# MultiWiiChassis.net
KiCad netlist of a schematic drawn in EAGLE
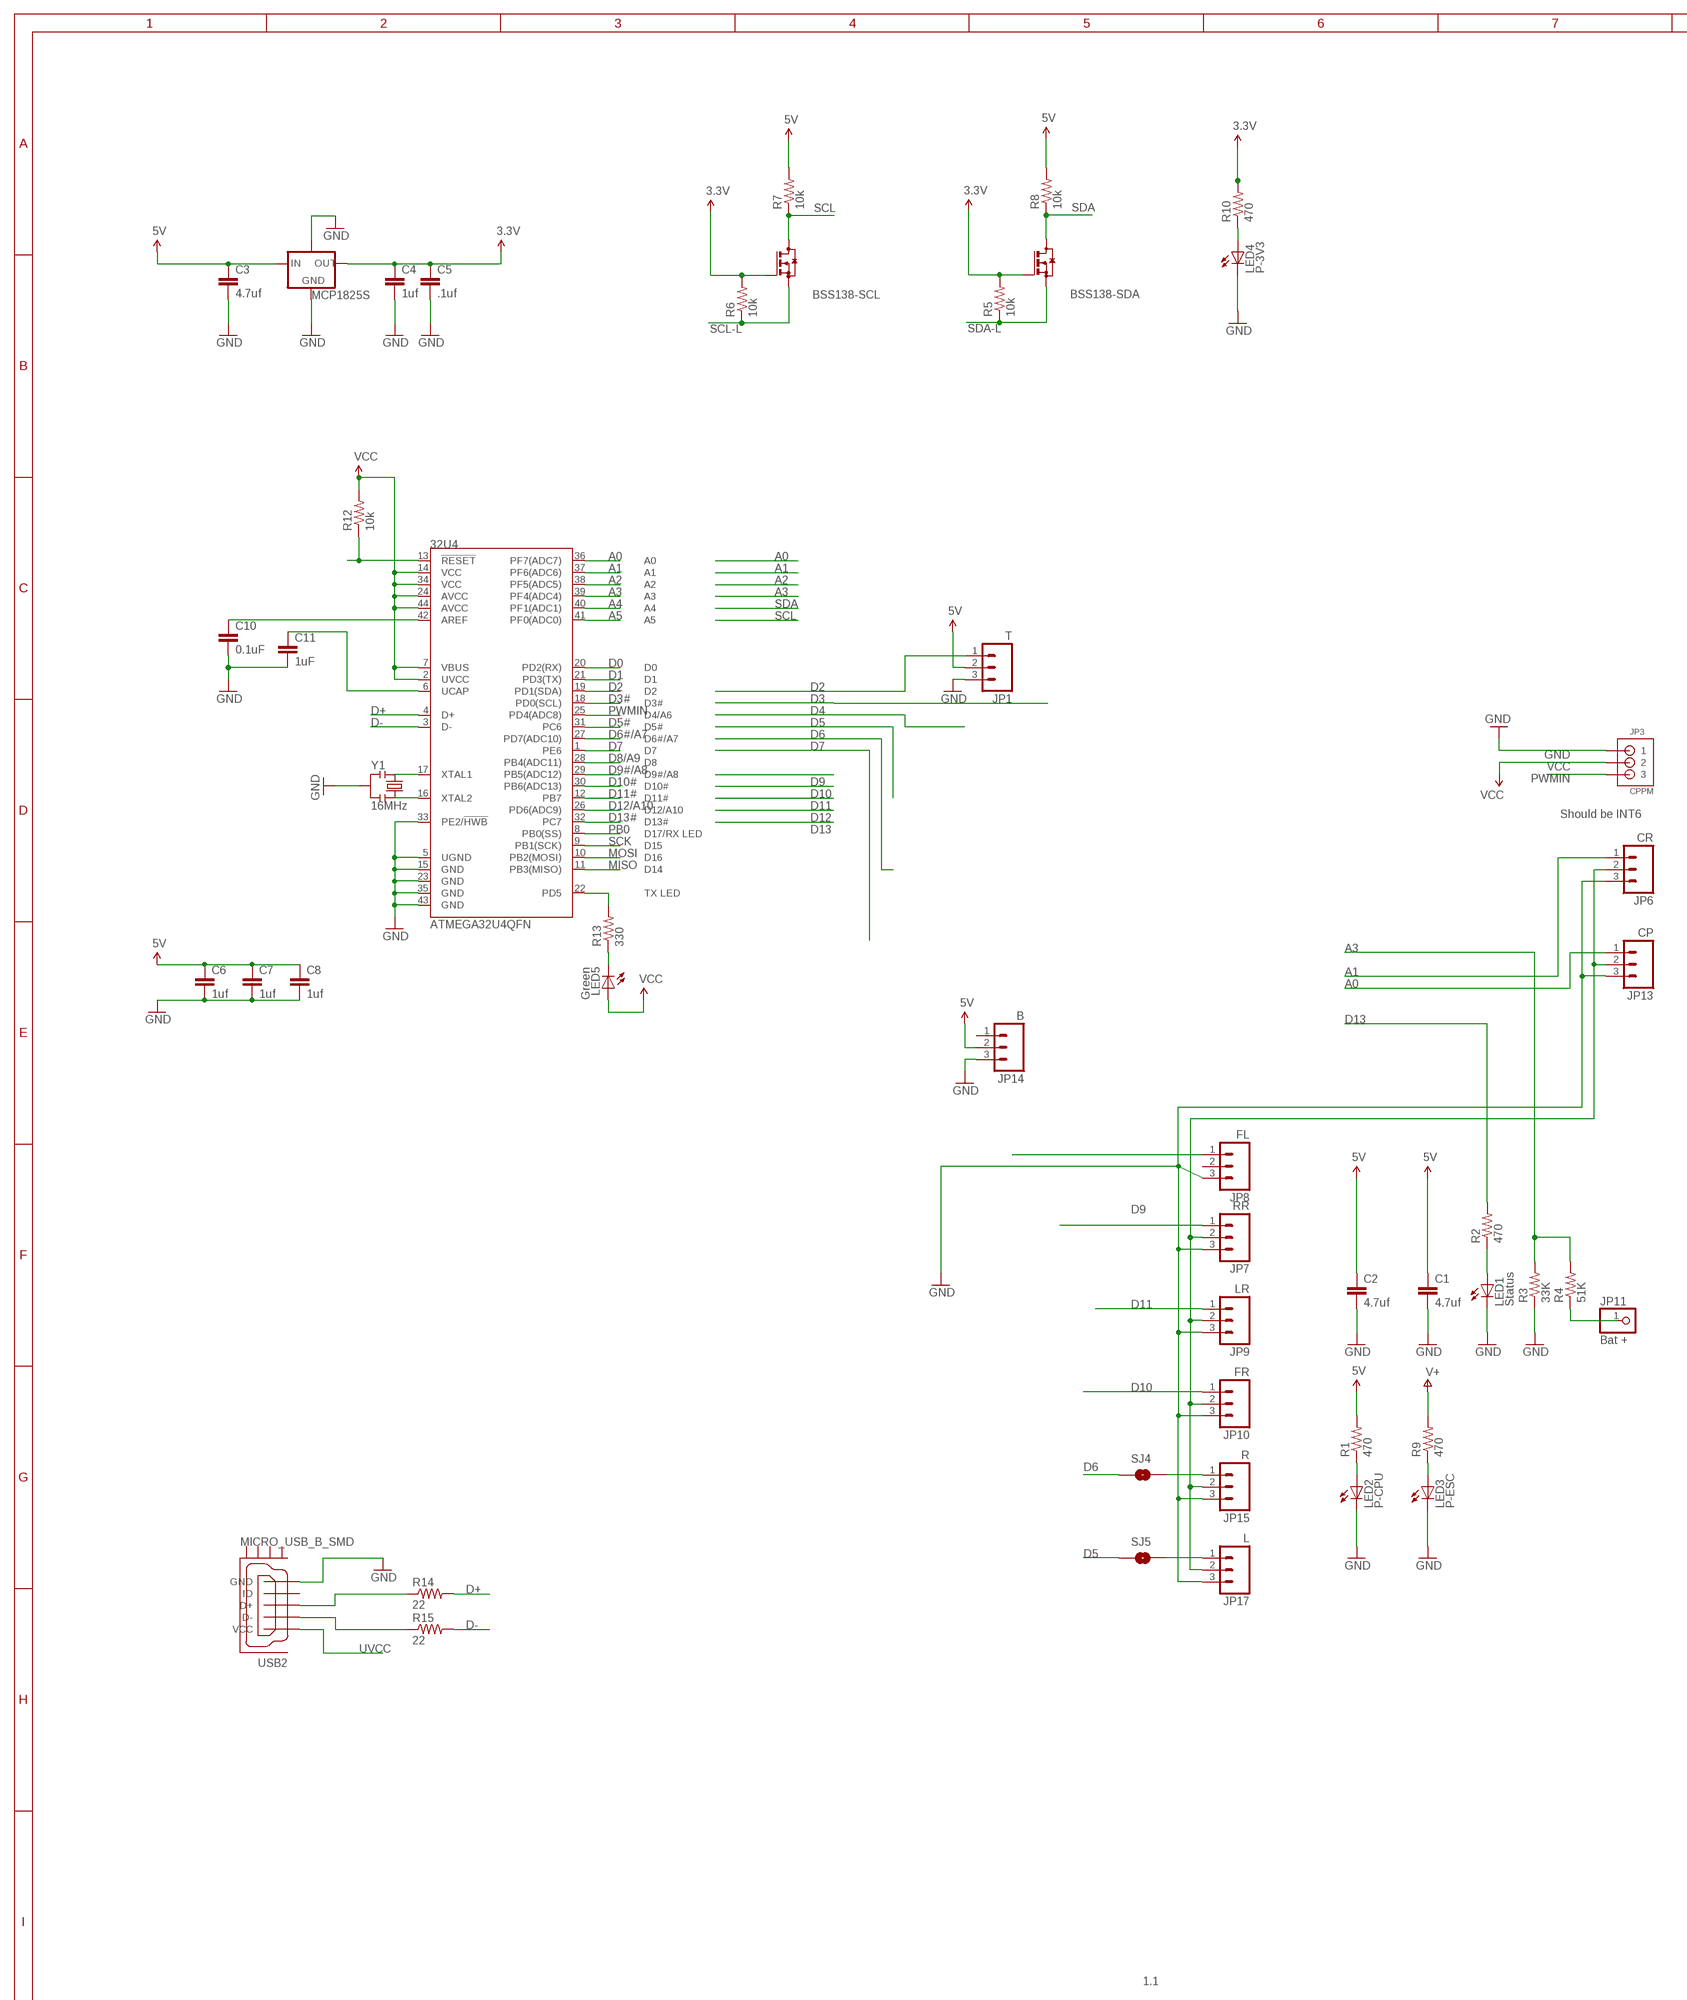
[diagram p0: schematic, sheet 1, part 1 of 2]
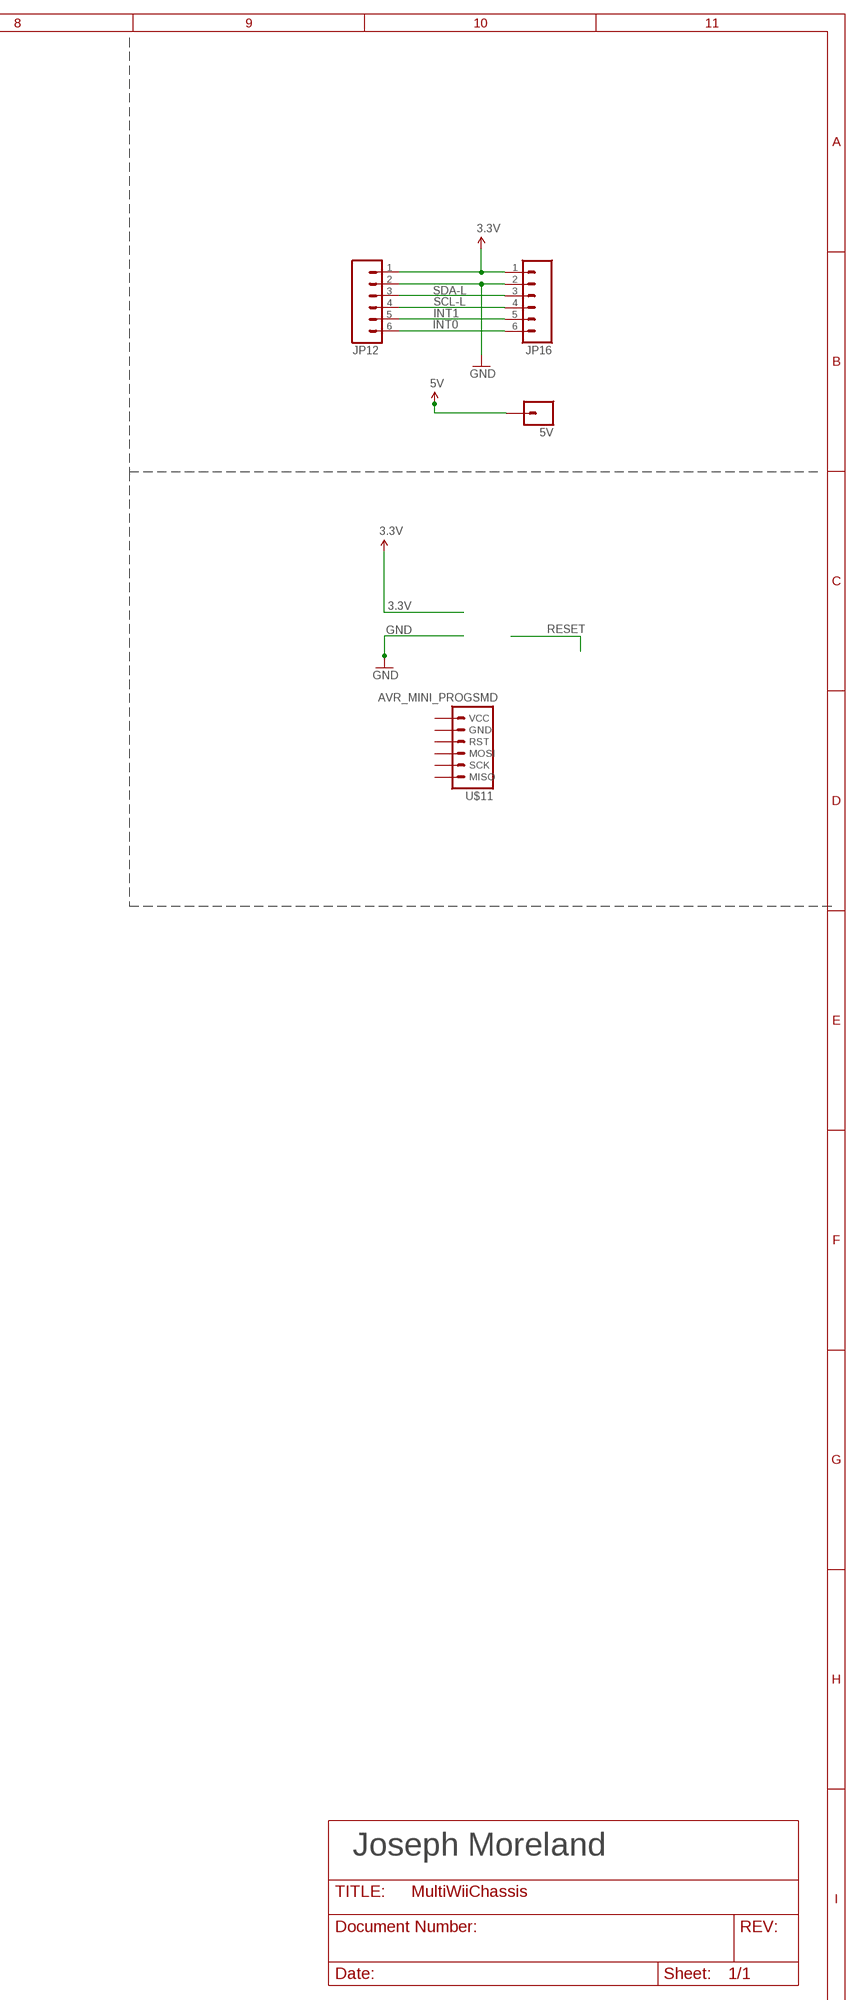
[diagram p1: schematic, sheet 1, part 2 of 2]

(export (version "E")
  (design (tool "Eeschema 10.0.6"))
  (components
    (comp (ref "5V")
      (value "M01PTH")
      (footprint "eagle-import:1X01")
      (libsource (lib "eagle-import") (part "M01PTH"))
    )
    (comp (ref "32U4")
      (value "ATMEGA32U4QFN")
      (footprint "eagle-import:SPARKFUN-DIGITALIC_QFN-44")
      (fields (field (name "PARTNO") "ATMEGA32U4-MU"))
      (libsource (lib "eagle-import") (part "ATMEGA32U4QFN"))
    )
    (comp (ref "BSS138-SCL")
      (value "BSS138BOTTOM")
      (footprint "eagle-import:SOT23_BOT")
      (libsource (lib "eagle-import") (part "BSS138BOTTOM"))
    )
    (comp (ref "BSS138-SDA")
      (value "BSS138BOTTOM")
      (footprint "eagle-import:SOT23_BOT")
      (libsource (lib "eagle-import") (part "BSS138BOTTOM"))
    )
    (comp (ref "C1")
      (value "4.7uf")
      (footprint "eagle-import:0603-CAP")
      (libsource (lib "eagle-import") (part "CAP0603-CAP"))
    )
    (comp (ref "C2")
      (value "4.7uf")
      (footprint "eagle-import:0603-CAP")
      (libsource (lib "eagle-import") (part "CAP0603-CAP"))
    )
    (comp (ref "C3")
      (value "4.7uf")
      (footprint "eagle-import:0603-CAP")
      (libsource (lib "eagle-import") (part "CAP0603-CAP"))
    )
    (comp (ref "C4")
      (value "1uf")
      (footprint "eagle-import:0603-CAP")
      (libsource (lib "eagle-import") (part "CAP0603-CAP"))
    )
    (comp (ref "C5")
      (value ".1uf")
      (footprint "eagle-import:0603-CAP")
      (libsource (lib "eagle-import") (part "CAP0603-CAP"))
    )
    (comp (ref "C6")
      (value "1uf")
      (footprint "eagle-import:0603-CAP")
      (libsource (lib "eagle-import") (part "CAP0603-CAP"))
    )
    (comp (ref "C7")
      (value "1uf")
      (footprint "eagle-import:0603-CAP")
      (libsource (lib "eagle-import") (part "CAP0603-CAP"))
    )
    (comp (ref "C8")
      (value "1uf")
      (footprint "eagle-import:0603-CAP")
      (libsource (lib "eagle-import") (part "CAP0603-CAP"))
    )
    (comp (ref "C10")
      (value "0.1uF")
      (footprint "eagle-import:0603-CAP")
      (fields (field (name "PARTNO") "C0603C104K8RACTU"))
      (libsource (lib "eagle-import") (part "SparkFun-Capacitors_CAP0603-CAP"))
    )
    (comp (ref "C11")
      (value "1uF")
      (footprint "eagle-import:0402-CAP")
      (fields (field (name "PARTNO") "LMK105BJ105KV-F"))
      (libsource (lib "eagle-import") (part "SparkFun-Capacitors_CAP0402-CAP"))
    )
    (comp (ref "JP1")
      (value "T")
      (footprint "eagle-import:1X03")
      (libsource (lib "eagle-import") (part "M03PTH"))
    )
    (comp (ref "JP3")
      (value "CPPM")
      (footprint "eagle-import:B3B-ZR")
      (fields (field (name "PARTNO") "M20-9990346"))
      (libsource (lib "eagle-import") (part "B3B-ZR"))
    )
    (comp (ref "JP6")
      (value "CR")
      (footprint "eagle-import:1X03")
      (libsource (lib "eagle-import") (part "M03PTH"))
    )
    (comp (ref "JP7")
      (value "RR")
      (footprint "eagle-import:1X03")
      (libsource (lib "eagle-import") (part "M03PTH"))
    )
    (comp (ref "JP8")
      (value "FL")
      (footprint "eagle-import:1X03")
      (libsource (lib "eagle-import") (part "M03PTH"))
    )
    (comp (ref "JP9")
      (value "LR")
      (footprint "eagle-import:1X03")
      (libsource (lib "eagle-import") (part "M03PTH"))
    )
    (comp (ref "JP10")
      (value "FR")
      (footprint "eagle-import:1X03")
      (libsource (lib "eagle-import") (part "M03PTH"))
    )
    (comp (ref "JP11")
      (value "Bat +")
      (footprint "eagle-import:1X01")
      (libsource (lib "eagle-import") (part "PINHD-1X1"))
    )
    (comp (ref "JP12")
      (value "M06LOCK")
      (footprint "eagle-import:1X06_LOCK")
      (libsource (lib "eagle-import") (part "M06LOCK"))
    )
    (comp (ref "JP13")
      (value "CP")
      (footprint "eagle-import:1X03")
      (libsource (lib "eagle-import") (part "M03PTH"))
    )
    (comp (ref "JP14")
      (value "B")
      (footprint "eagle-import:1X03")
      (libsource (lib "eagle-import") (part "M03PTH"))
    )
    (comp (ref "JP15")
      (value "R")
      (footprint "eagle-import:1X03")
      (libsource (lib "eagle-import") (part "M03PTH"))
    )
    (comp (ref "JP16")
      (value "M06LOCK")
      (footprint "eagle-import:1X06_LOCK")
      (libsource (lib "eagle-import") (part "M06LOCK"))
    )
    (comp (ref "JP17")
      (value "L")
      (footprint "eagle-import:1X03")
      (libsource (lib "eagle-import") (part "M03PTH"))
    )
    (comp (ref "LED1")
      (value "Status")
      (footprint "eagle-import:LED-1206")
      (libsource (lib "eagle-import") (part "LED1206"))
    )
    (comp (ref "LED2")
      (value "P-CPU")
      (footprint "eagle-import:LED-1206")
      (libsource (lib "eagle-import") (part "LED1206"))
    )
    (comp (ref "LED3")
      (value "P-ESC")
      (footprint "eagle-import:LED-1206")
      (libsource (lib "eagle-import") (part "LED1206"))
    )
    (comp (ref "LED4")
      (value "P-3V3")
      (footprint "eagle-import:LED-1206")
      (libsource (lib "eagle-import") (part "LED1206"))
    )
    (comp (ref "LED5")
      (value "Green")
      (footprint "eagle-import:LED-0603")
      (fields (field (name "PARTNO") "LTST-C190KGKT"))
      (libsource (lib "eagle-import") (part "SparkFun-LED_LED0603"))
    )
    (comp (ref "MCP1825S")
      (value "V_REG_MCP1825S")
      (footprint "eagle-import:SOT223_BOT")
      (libsource (lib "eagle-import") (part "V_REG_MCP1825SBOTTOM"))
    )
    (comp (ref "R1")
      (value "470")
      (footprint "eagle-import:0603-RES")
      (libsource (lib "eagle-import") (part "RESISTOR0603-RES"))
    )
    (comp (ref "R2")
      (value "470")
      (footprint "eagle-import:0603-RES")
      (libsource (lib "eagle-import") (part "RESISTOR0603-RES"))
    )
    (comp (ref "R3")
      (value "33K")
      (footprint "eagle-import:0603-RES")
      (libsource (lib "eagle-import") (part "RESISTOR0603-RES"))
    )
    (comp (ref "R4")
      (value "51K")
      (footprint "eagle-import:0805")
      (libsource (lib "eagle-import") (part "RESISTOR0805-RES"))
    )
    (comp (ref "R5")
      (value "10k")
      (footprint "eagle-import:0805")
      (libsource (lib "eagle-import") (part "RESISTOR0805-RES"))
    )
    (comp (ref "R6")
      (value "10k")
      (footprint "eagle-import:0805")
      (libsource (lib "eagle-import") (part "RESISTOR0805-RES"))
    )
    (comp (ref "R7")
      (value "10k")
      (footprint "eagle-import:0805")
      (libsource (lib "eagle-import") (part "RESISTOR0805-RES"))
    )
    (comp (ref "R8")
      (value "10k")
      (footprint "eagle-import:0805")
      (libsource (lib "eagle-import") (part "RESISTOR0805-RES"))
    )
    (comp (ref "R9")
      (value "470")
      (footprint "eagle-import:0805")
      (libsource (lib "eagle-import") (part "RESISTOR0805-RES"))
    )
    (comp (ref "R10")
      (value "470")
      (footprint "eagle-import:0805")
      (libsource (lib "eagle-import") (part "RESISTOR0805-RES"))
    )
    (comp (ref "R12")
      (value "10k")
      (footprint "eagle-import:0402-RES")
      (fields (field (name "PARTNO") "CRCW040210K0FKED"))
      (libsource (lib "eagle-import") (part "SparkFun-Resistors_RESISTOR0402-RES"))
    )
    (comp (ref "R13")
      (value "330")
      (footprint "eagle-import:0402-RES")
      (fields (field (name "PARTNO") "CRCW0402330RJNED"))
      (libsource (lib "eagle-import") (part "SparkFun-Resistors_RESISTOR0402-RES"))
    )
    (comp (ref "R14")
      (value "22")
      (footprint "eagle-import:0402-RES")
      (fields (field (name "PARTNO") "CRCW040222R0JNED"))
      (libsource (lib "eagle-import") (part "SparkFun-Resistors_RESISTOR0402-RES"))
    )
    (comp (ref "R15")
      (value "22")
      (footprint "eagle-import:0402-RES")
      (fields (field (name "PARTNO") "CRCW040222R0JNED"))
      (libsource (lib "eagle-import") (part "SparkFun-Resistors_RESISTOR0402-RES"))
    )
    (comp (ref "SJ4")
      (value "SOLDERJUMPERNO")
      (footprint "eagle-import:SJ_2S-NO")
      (libsource (lib "eagle-import") (part "SOLDERJUMPERNO"))
    )
    (comp (ref "SJ5")
      (value "SOLDERJUMPERNO")
      (footprint "eagle-import:SJ_2S-NO")
      (libsource (lib "eagle-import") (part "SOLDERJUMPERNO"))
    )
    (comp (ref "U$11")
      (value "AVR_MINI_PROGSMD")
      (footprint "eagle-import:AVR_MINI_PROG")
      (libsource (lib "eagle-import") (part "AVR_MINI_PROGSMD"))
    )
    (comp (ref "USB2")
      (value "MICRO_USB_B_SMD")
      (footprint "eagle-import:MOLEX_MICRO_USB_B_BOTTOM_MOUNT")
      (fields (field (name "PARTNO") "473460001"))
      (libsource (lib "eagle-import") (part "MICRO_USB_B_SMD"))
    )
    (comp (ref "Y1")
      (value "16MHz")
      (footprint "eagle-import:RESONATOR-SMD")
      (fields (field (name "PARTNO") "CSTCE16M0V53-R0"))
      (libsource (lib "eagle-import") (part "RESONATOR16MHZ"))
    )
  )
  (nets
    (net (code "1") (name "/A0") (class "Default")
      (node (ref "32U4") (pin "36") (pinfunction "PF7(ADC7)_36") (pintype "bidirectional"))
      (node (ref "JP13") (pin "1") (pinfunction "1_1") (pintype "passive"))
    )
    (net (code "2") (name "/A1") (class "Default")
      (node (ref "32U4") (pin "37") (pinfunction "PF6(ADC6)_37") (pintype "bidirectional"))
      (node (ref "JP6") (pin "1") (pinfunction "1_1") (pintype "passive"))
    )
    (net (code "3") (name "/A2") (class "Default")
      (node (ref "32U4") (pin "38") (pinfunction "PF5(ADC5)_38") (pintype "bidirectional"))
    )
    (net (code "4") (name "/A3") (class "Default")
      (node (ref "32U4") (pin "39") (pinfunction "PF4(ADC4)_39") (pintype "bidirectional"))
      (node (ref "R3") (pin "2") (pinfunction "2_2") (pintype "passive"))
      (node (ref "R4") (pin "2") (pinfunction "2_2") (pintype "passive"))
    )
    (net (code "5") (name "/A4") (class "Default")
      (node (ref "32U4") (pin "40") (pinfunction "PF1(ADC1)_40") (pintype "bidirectional"))
    )
    (net (code "6") (name "/A5") (class "Default")
      (node (ref "32U4") (pin "41") (pinfunction "PF0(ADC0)_41") (pintype "bidirectional"))
    )
    (net (code "7") (name "/D+") (class "Default")
      (node (ref "32U4") (pin "4") (pinfunction "D+_4") (pintype "bidirectional"))
      (node (ref "R14") (pin "2") (pinfunction "2_2") (pintype "passive"))
    )
    (net (code "8") (name "/D-") (class "Default")
      (node (ref "32U4") (pin "3") (pinfunction "D-_3") (pintype "bidirectional"))
      (node (ref "R15") (pin "2") (pinfunction "2_2") (pintype "passive"))
    )
    (net (code "9") (name "/D0") (class "Default")
      (node (ref "32U4") (pin "20") (pinfunction "PD2(RX)_20") (pintype "bidirectional"))
    )
    (net (code "10") (name "/D1") (class "Default")
      (node (ref "32U4") (pin "21") (pinfunction "PD3(TX)_21") (pintype "bidirectional"))
    )
    (net (code "11") (name "/D2") (class "Default")
      (node (ref "32U4") (pin "19") (pinfunction "PD1(SDA)_19") (pintype "bidirectional"))
      (node (ref "JP1") (pin "1") (pinfunction "1_1") (pintype "passive"))
    )
    (net (code "12") (name "/D3") (class "Default")
      (node (ref "JP8") (pin "1") (pinfunction "1_1") (pintype "passive"))
    )
    (net (code "13") (name "/D3#") (class "Default")
      (node (ref "32U4") (pin "18") (pinfunction "PD0(SCL)_18") (pintype "bidirectional"))
    )
    (net (code "15") (name "/D5") (class "Default")
      (node (ref "SJ5") (pin "1") (pinfunction "1_1") (pintype "passive"))
    )
    (net (code "16") (name "/D5#") (class "Default")
      (node (ref "32U4") (pin "31") (pinfunction "PC6_31") (pintype "bidirectional"))
    )
    (net (code "17") (name "/D6") (class "Default")
      (node (ref "SJ4") (pin "1") (pinfunction "1_1") (pintype "passive"))
    )
    (net (code "18") (name "/D6#{slash}A7") (class "Default")
      (node (ref "32U4") (pin "27") (pinfunction "PD7(ADC10)_27") (pintype "bidirectional"))
    )
    (net (code "19") (name "/D7") (class "Default")
      (node (ref "32U4") (pin "1") (pinfunction "PE6_1") (pintype "bidirectional"))
    )
    (net (code "20") (name "/D8{slash}A9") (class "Default")
      (node (ref "32U4") (pin "28") (pinfunction "PB4(ADC11)_28") (pintype "bidirectional"))
    )
    (net (code "21") (name "/D9") (class "Default")
      (node (ref "JP7") (pin "1") (pinfunction "1_1") (pintype "passive"))
    )
    (net (code "22") (name "/D9#{slash}A8") (class "Default")
      (node (ref "32U4") (pin "29") (pinfunction "PB5(ADC12)_29") (pintype "bidirectional"))
    )
    (net (code "23") (name "/D10") (class "Default")
      (node (ref "JP10") (pin "1") (pinfunction "1_1") (pintype "passive"))
    )
    (net (code "24") (name "/D10#") (class "Default")
      (node (ref "32U4") (pin "30") (pinfunction "PB6(ADC13)_30") (pintype "bidirectional"))
    )
    (net (code "25") (name "/D11") (class "Default")
      (node (ref "JP9") (pin "1") (pinfunction "1_1") (pintype "passive"))
    )
    (net (code "26") (name "/D11#") (class "Default")
      (node (ref "32U4") (pin "12") (pinfunction "PB7_12") (pintype "bidirectional"))
    )
    (net (code "28") (name "/D12{slash}A10") (class "Default")
      (node (ref "32U4") (pin "26") (pinfunction "PD6(ADC9)_26") (pintype "bidirectional"))
    )
    (net (code "29") (name "/D13") (class "Default")
      (node (ref "R2") (pin "2") (pinfunction "2_2") (pintype "passive"))
    )
    (net (code "30") (name "/D13#") (class "Default")
      (node (ref "32U4") (pin "32") (pinfunction "PC7_32") (pintype "bidirectional"))
    )
    (net (code "31") (name "/INT0") (class "Default")
      (node (ref "JP12") (pin "6") (pinfunction "6_6") (pintype "passive"))
      (node (ref "JP16") (pin "6") (pinfunction "6_6") (pintype "passive"))
    )
    (net (code "32") (name "/INT1") (class "Default")
      (node (ref "JP12") (pin "5") (pinfunction "5_5") (pintype "passive"))
      (node (ref "JP16") (pin "5") (pinfunction "5_5") (pintype "passive"))
    )
    (net (code "33") (name "/MISO") (class "Default")
      (node (ref "32U4") (pin "11") (pinfunction "PB3(MISO)_11") (pintype "bidirectional"))
    )
    (net (code "34") (name "/MOSI") (class "Default")
      (node (ref "32U4") (pin "10") (pinfunction "PB2(MOSI)_10") (pintype "bidirectional"))
    )
    (net (code "35") (name "/PB0") (class "Default")
      (node (ref "32U4") (pin "8") (pinfunction "PB0(SS)_8") (pintype "bidirectional"))
    )
    (net (code "36") (name "/PWMIN") (class "Default")
      (node (ref "32U4") (pin "25") (pinfunction "PD4(ADC8)_25") (pintype "bidirectional"))
      (node (ref "JP3") (pin "3") (pinfunction "3_3") (pintype "bidirectional"))
    )
    (net (code "38") (name "/SCK") (class "Default")
      (node (ref "32U4") (pin "9") (pinfunction "PB1(SCK)_9") (pintype "bidirectional"))
    )
    (net (code "39") (name "/SCL") (class "Default")
      (node (ref "BSS138-SCL") (pin "D") (pinfunction "D_D") (pintype "passive"))
      (node (ref "R7") (pin "1") (pinfunction "1_1") (pintype "passive"))
    )
    (net (code "40") (name "/SCL-L") (class "Default")
      (node (ref "BSS138-SCL") (pin "S") (pinfunction "S_S") (pintype "passive"))
      (node (ref "JP12") (pin "4") (pinfunction "4_4") (pintype "passive"))
      (node (ref "JP16") (pin "4") (pinfunction "4_4") (pintype "passive"))
      (node (ref "R6") (pin "1") (pinfunction "1_1") (pintype "passive"))
    )
    (net (code "41") (name "/SDA") (class "Default")
      (node (ref "BSS138-SDA") (pin "D") (pinfunction "D_D") (pintype "passive"))
      (node (ref "R8") (pin "1") (pinfunction "1_1") (pintype "passive"))
    )
    (net (code "42") (name "/SDA-L") (class "Default")
      (node (ref "BSS138-SDA") (pin "S") (pinfunction "S_S") (pintype "passive"))
      (node (ref "JP12") (pin "3") (pinfunction "3_3") (pintype "passive"))
      (node (ref "JP16") (pin "3") (pinfunction "3_3") (pintype "passive"))
      (node (ref "R5") (pin "1") (pinfunction "1_1") (pintype "passive"))
    )
    (net (code "43") (name "/UVCC") (class "Default")
      (node (ref "USB2") (pin "1") (pinfunction "VCC_1") (pintype "input"))
    )
    (net (code "44") (name "3.3V") (class "Default")
      (node (ref "BSS138-SCL") (pin "G") (pinfunction "G_G") (pintype "passive"))
      (node (ref "BSS138-SDA") (pin "G") (pinfunction "G_G") (pintype "passive"))
      (node (ref "C4") (pin "1") (pinfunction "1_1") (pintype "passive"))
      (node (ref "C5") (pin "1") (pinfunction "1_1") (pintype "passive"))
      (node (ref "JP12") (pin "1") (pinfunction "1_1") (pintype "passive"))
      (node (ref "JP16") (pin "1") (pinfunction "1_1") (pintype "passive"))
      (node (ref "MCP1825S") (pin "3") (pinfunction "OUT_3") (pintype "power_in"))
      (node (ref "R10") (pin "2") (pinfunction "2_2") (pintype "passive"))
      (node (ref "R5") (pin "2") (pinfunction "2_2") (pintype "passive"))
      (node (ref "R6") (pin "2") (pinfunction "2_2") (pintype "passive"))
    )
    (net (code "45") (name "5V") (class "Default")
      (node (ref "5V") (pin "1") (pinfunction "1_1") (pintype "passive"))
      (node (ref "C1") (pin "1") (pinfunction "1_1") (pintype "passive"))
      (node (ref "C2") (pin "1") (pinfunction "1_1") (pintype "passive"))
      (node (ref "C3") (pin "1") (pinfunction "1_1") (pintype "passive"))
      (node (ref "C6") (pin "1") (pinfunction "1_1") (pintype "passive"))
      (node (ref "C7") (pin "1") (pinfunction "1_1") (pintype "passive"))
      (node (ref "C8") (pin "1") (pinfunction "1_1") (pintype "passive"))
      (node (ref "JP1") (pin "2") (pinfunction "2_2") (pintype "passive"))
      (node (ref "JP14") (pin "2") (pinfunction "2_2") (pintype "passive"))
      (node (ref "MCP1825S") (pin "1") (pinfunction "IN_1") (pintype "input"))
      (node (ref "R1") (pin "2") (pinfunction "2_2") (pintype "passive"))
      (node (ref "R7") (pin "2") (pinfunction "2_2") (pintype "passive"))
      (node (ref "R8") (pin "2") (pinfunction "2_2") (pintype "passive"))
    )
    (net (code "46") (name "GND") (class "Default")
      (node (ref "32U4") (pin "15") (pinfunction "GND_15") (pintype "bidirectional"))
      (node (ref "32U4") (pin "23") (pinfunction "GND_23") (pintype "bidirectional"))
      (node (ref "32U4") (pin "33") (pinfunction "PE2/~{HWB}_33") (pintype "bidirectional"))
      (node (ref "32U4") (pin "35") (pinfunction "GND_35") (pintype "bidirectional"))
      (node (ref "32U4") (pin "43") (pinfunction "GND_43") (pintype "bidirectional"))
      (node (ref "32U4") (pin "5") (pinfunction "UGND_5") (pintype "bidirectional"))
      (node (ref "C1") (pin "2") (pinfunction "2_2") (pintype "passive"))
      (node (ref "C10") (pin "2") (pinfunction "2_2") (pintype "passive"))
      (node (ref "C11") (pin "2") (pinfunction "2_2") (pintype "passive"))
      (node (ref "C2") (pin "2") (pinfunction "2_2") (pintype "passive"))
      (node (ref "C3") (pin "2") (pinfunction "2_2") (pintype "passive"))
      (node (ref "C4") (pin "2") (pinfunction "2_2") (pintype "passive"))
      (node (ref "C5") (pin "2") (pinfunction "2_2") (pintype "passive"))
      (node (ref "C6") (pin "2") (pinfunction "2_2") (pintype "passive"))
      (node (ref "C7") (pin "2") (pinfunction "2_2") (pintype "passive"))
      (node (ref "C8") (pin "2") (pinfunction "2_2") (pintype "passive"))
      (node (ref "JP1") (pin "3") (pinfunction "3_3") (pintype "passive"))
      (node (ref "JP10") (pin "3") (pinfunction "3_3") (pintype "passive"))
      (node (ref "JP12") (pin "2") (pinfunction "2_2") (pintype "passive"))
      (node (ref "JP13") (pin "3") (pinfunction "3_3") (pintype "passive"))
      (node (ref "JP14") (pin "3") (pinfunction "3_3") (pintype "passive"))
      (node (ref "JP15") (pin "3") (pinfunction "3_3") (pintype "passive"))
      (node (ref "JP16") (pin "2") (pinfunction "2_2") (pintype "passive"))
      (node (ref "JP17") (pin "3") (pinfunction "3_3") (pintype "passive"))
      (node (ref "JP3") (pin "1") (pinfunction "1_1") (pintype "bidirectional"))
      (node (ref "JP6") (pin "3") (pinfunction "3_3") (pintype "passive"))
      (node (ref "JP7") (pin "3") (pinfunction "3_3") (pintype "passive"))
      (node (ref "JP8") (pin "3") (pinfunction "3_3") (pintype "passive"))
      (node (ref "JP9") (pin "3") (pinfunction "3_3") (pintype "passive"))
      (node (ref "LED1") (pin "C") (pinfunction "C_C") (pintype "passive"))
      (node (ref "LED2") (pin "C") (pinfunction "C_C") (pintype "passive"))
      (node (ref "LED3") (pin "C") (pinfunction "C_C") (pintype "passive"))
      (node (ref "LED4") (pin "C") (pinfunction "C_C") (pintype "passive"))
      (node (ref "MCP1825S") (pin "2") (pinfunction "GND_2") (pintype "input"))
      (node (ref "MCP1825S") (pin "GNDPAD") (pinfunction "GNDPAD_GNDPAD") (pintype "bidirectional"))
      (node (ref "R3") (pin "1") (pinfunction "1_1") (pintype "passive"))
      (node (ref "USB2") (pin "5") (pinfunction "GND_5") (pintype "input"))
      (node (ref "Y1") (pin "2") (pinfunction "2_2") (pintype "passive"))
    )
    (net (code "47") (name "Net-(32U4-AREF)") (class "Default")
      (node (ref "32U4") (pin "42") (pinfunction "AREF_42") (pintype "bidirectional"))
      (node (ref "C10") (pin "1") (pinfunction "1_1") (pintype "passive"))
    )
    (net (code "48") (name "Net-(32U4-PD5)") (class "Default")
      (node (ref "32U4") (pin "22") (pinfunction "PD5_22") (pintype "bidirectional"))
      (node (ref "R13") (pin "2") (pinfunction "2_2") (pintype "passive"))
    )
    (net (code "49") (name "Net-(32U4-UCAP)") (class "Default")
      (node (ref "32U4") (pin "6") (pinfunction "UCAP_6") (pintype "bidirectional"))
      (node (ref "C11") (pin "1") (pinfunction "1_1") (pintype "passive"))
    )
    (net (code "50") (name "Net-(32U4-XTAL1)") (class "Default")
      (node (ref "32U4") (pin "17") (pinfunction "XTAL1_17") (pintype "bidirectional"))
      (node (ref "Y1") (pin "1") (pinfunction "1_1") (pintype "passive"))
    )
    (net (code "51") (name "Net-(32U4-XTAL2)") (class "Default")
      (node (ref "32U4") (pin "16") (pinfunction "XTAL2_16") (pintype "bidirectional"))
      (node (ref "Y1") (pin "3") (pinfunction "3_3") (pintype "passive"))
    )
    (net (code "52") (name "Net-(32U4-~{RESET})") (class "Default")
      (node (ref "32U4") (pin "13") (pinfunction "~{RESET}_13") (pintype "bidirectional"))
      (node (ref "R12") (pin "1") (pinfunction "1_1") (pintype "passive"))
    )
    (net (code "53") (name "Net-(JP11-Pad1)") (class "Default")
      (node (ref "JP11") (pin "1") (pinfunction "1_1") (pintype "passive"))
      (node (ref "R4") (pin "1") (pinfunction "1_1") (pintype "passive"))
    )
    (net (code "54") (name "Net-(JP15-Pad1)") (class "Default")
      (node (ref "JP15") (pin "1") (pinfunction "1_1") (pintype "passive"))
      (node (ref "SJ4") (pin "2") (pinfunction "2_2") (pintype "passive"))
    )
    (net (code "55") (name "Net-(JP17-Pad1)") (class "Default")
      (node (ref "JP17") (pin "1") (pinfunction "1_1") (pintype "passive"))
      (node (ref "SJ5") (pin "2") (pinfunction "2_2") (pintype "passive"))
    )
    (net (code "56") (name "Net-(LED1-PadA)") (class "Default")
      (node (ref "LED1") (pin "A") (pinfunction "A_A") (pintype "passive"))
      (node (ref "R2") (pin "1") (pinfunction "1_1") (pintype "passive"))
    )
    (net (code "57") (name "Net-(LED2-PadA)") (class "Default")
      (node (ref "LED2") (pin "A") (pinfunction "A_A") (pintype "passive"))
      (node (ref "R1") (pin "1") (pinfunction "1_1") (pintype "passive"))
    )
    (net (code "58") (name "Net-(LED3-PadA)") (class "Default")
      (node (ref "LED3") (pin "A") (pinfunction "A_A") (pintype "passive"))
      (node (ref "R9") (pin "1") (pinfunction "1_1") (pintype "passive"))
    )
    (net (code "59") (name "Net-(LED4-PadA)") (class "Default")
      (node (ref "LED4") (pin "A") (pinfunction "A_A") (pintype "passive"))
      (node (ref "R10") (pin "1") (pinfunction "1_1") (pintype "passive"))
    )
    (net (code "60") (name "Net-(LED5-PadC)") (class "Default")
      (node (ref "LED5") (pin "C") (pinfunction "C_C") (pintype "passive"))
      (node (ref "R13") (pin "1") (pinfunction "1_1") (pintype "passive"))
    )
    (net (code "61") (name "Net-(USB2-D+)") (class "Default")
      (node (ref "R14") (pin "1") (pinfunction "1_1") (pintype "passive"))
      (node (ref "USB2") (pin "3") (pinfunction "D+_3") (pintype "input"))
    )
    (net (code "62") (name "Net-(USB2-D-)") (class "Default")
      (node (ref "R15") (pin "1") (pinfunction "1_1") (pintype "passive"))
      (node (ref "USB2") (pin "2") (pinfunction "D-_2") (pintype "input"))
    )
    (net (code "63") (name "V+") (class "Default")
      (node (ref "JP10") (pin "2") (pinfunction "2_2") (pintype "passive"))
      (node (ref "JP13") (pin "2") (pinfunction "2_2") (pintype "passive"))
      (node (ref "JP15") (pin "2") (pinfunction "2_2") (pintype "passive"))
      (node (ref "JP17") (pin "2") (pinfunction "2_2") (pintype "passive"))
      (node (ref "JP6") (pin "2") (pinfunction "2_2") (pintype "passive"))
      (node (ref "JP7") (pin "2") (pinfunction "2_2") (pintype "passive"))
      (node (ref "JP9") (pin "2") (pinfunction "2_2") (pintype "passive"))
      (node (ref "R9") (pin "2") (pinfunction "2_2") (pintype "passive"))
    )
    (net (code "64") (name "VCC") (class "Default")
      (node (ref "32U4") (pin "14") (pinfunction "VCC_14") (pintype "bidirectional"))
      (node (ref "32U4") (pin "2") (pinfunction "UVCC_2") (pintype "bidirectional"))
      (node (ref "32U4") (pin "24") (pinfunction "AVCC_24") (pintype "bidirectional"))
      (node (ref "32U4") (pin "34") (pinfunction "VCC_34") (pintype "bidirectional"))
      (node (ref "32U4") (pin "44") (pinfunction "AVCC_44") (pintype "bidirectional"))
      (node (ref "32U4") (pin "7") (pinfunction "VBUS_7") (pintype "bidirectional"))
      (node (ref "JP3") (pin "2") (pinfunction "2_2") (pintype "bidirectional"))
      (node (ref "LED5") (pin "A") (pinfunction "A_A") (pintype "passive"))
      (node (ref "R12") (pin "2") (pinfunction "2_2") (pintype "passive"))
    )
    (net (code "65") (name "unconnected-(JP8-Pad2)") (class "Default")
      (node (ref "JP8") (pin "2") (pinfunction "2_2") (pintype "passive"))
    )
    (net (code "66") (name "unconnected-(JP14-Pad1)") (class "Default")
      (node (ref "JP14") (pin "1") (pinfunction "1_1") (pintype "passive"))
    )
    (net (code "67") (name "unconnected-(U$11-GND-Pad2)") (class "Default")
      (node (ref "U$11") (pin "2") (pinfunction "GND_2") (pintype "passive"))
    )
    (net (code "68") (name "unconnected-(U$11-MISO-Pad6)") (class "Default")
      (node (ref "U$11") (pin "6") (pinfunction "MISO_6") (pintype "passive"))
    )
    (net (code "69") (name "unconnected-(U$11-MOSI-Pad4)") (class "Default")
      (node (ref "U$11") (pin "4") (pinfunction "MOSI_4") (pintype "passive"))
    )
    (net (code "70") (name "unconnected-(U$11-RST-Pad3)") (class "Default")
      (node (ref "U$11") (pin "3") (pinfunction "RST_3") (pintype "passive"))
    )
    (net (code "71") (name "unconnected-(U$11-SCK-Pad5)") (class "Default")
      (node (ref "U$11") (pin "5") (pinfunction "SCK_5") (pintype "passive"))
    )
    (net (code "72") (name "unconnected-(U$11-VCC-Pad1)") (class "Default")
      (node (ref "U$11") (pin "1") (pinfunction "VCC_1") (pintype "passive"))
    )
    (net (code "73") (name "unconnected-(USB2-ID-Pad4)") (class "Default")
      (node (ref "USB2") (pin "4") (pinfunction "ID_4") (pintype "input"))
    )
    (net (code "74") (name "unconnected-(USB2-PadGND1)") (class "Default")
      (node (ref "USB2") (pin "GND1") (pinfunction "GND1_GND1") (pintype "bidirectional"))
    )
    (net (code "75") (name "unconnected-(USB2-PadGND2)") (class "Default")
      (node (ref "USB2") (pin "GND2") (pinfunction "GND2_GND2") (pintype "bidirectional"))
    )
    (net (code "76") (name "unconnected-(USB2-PadGND3)") (class "Default")
      (node (ref "USB2") (pin "GND3") (pinfunction "GND3_GND3") (pintype "bidirectional"))
    )
    (net (code "77") (name "unconnected-(USB2-PadGND4)") (class "Default")
      (node (ref "USB2") (pin "GND4") (pinfunction "GND4_GND4") (pintype "bidirectional"))
    )
  )
)
